# USB_Tester_STM32F429-DISC1.net
KiCad netlist of a schematic drawn in EAGLE
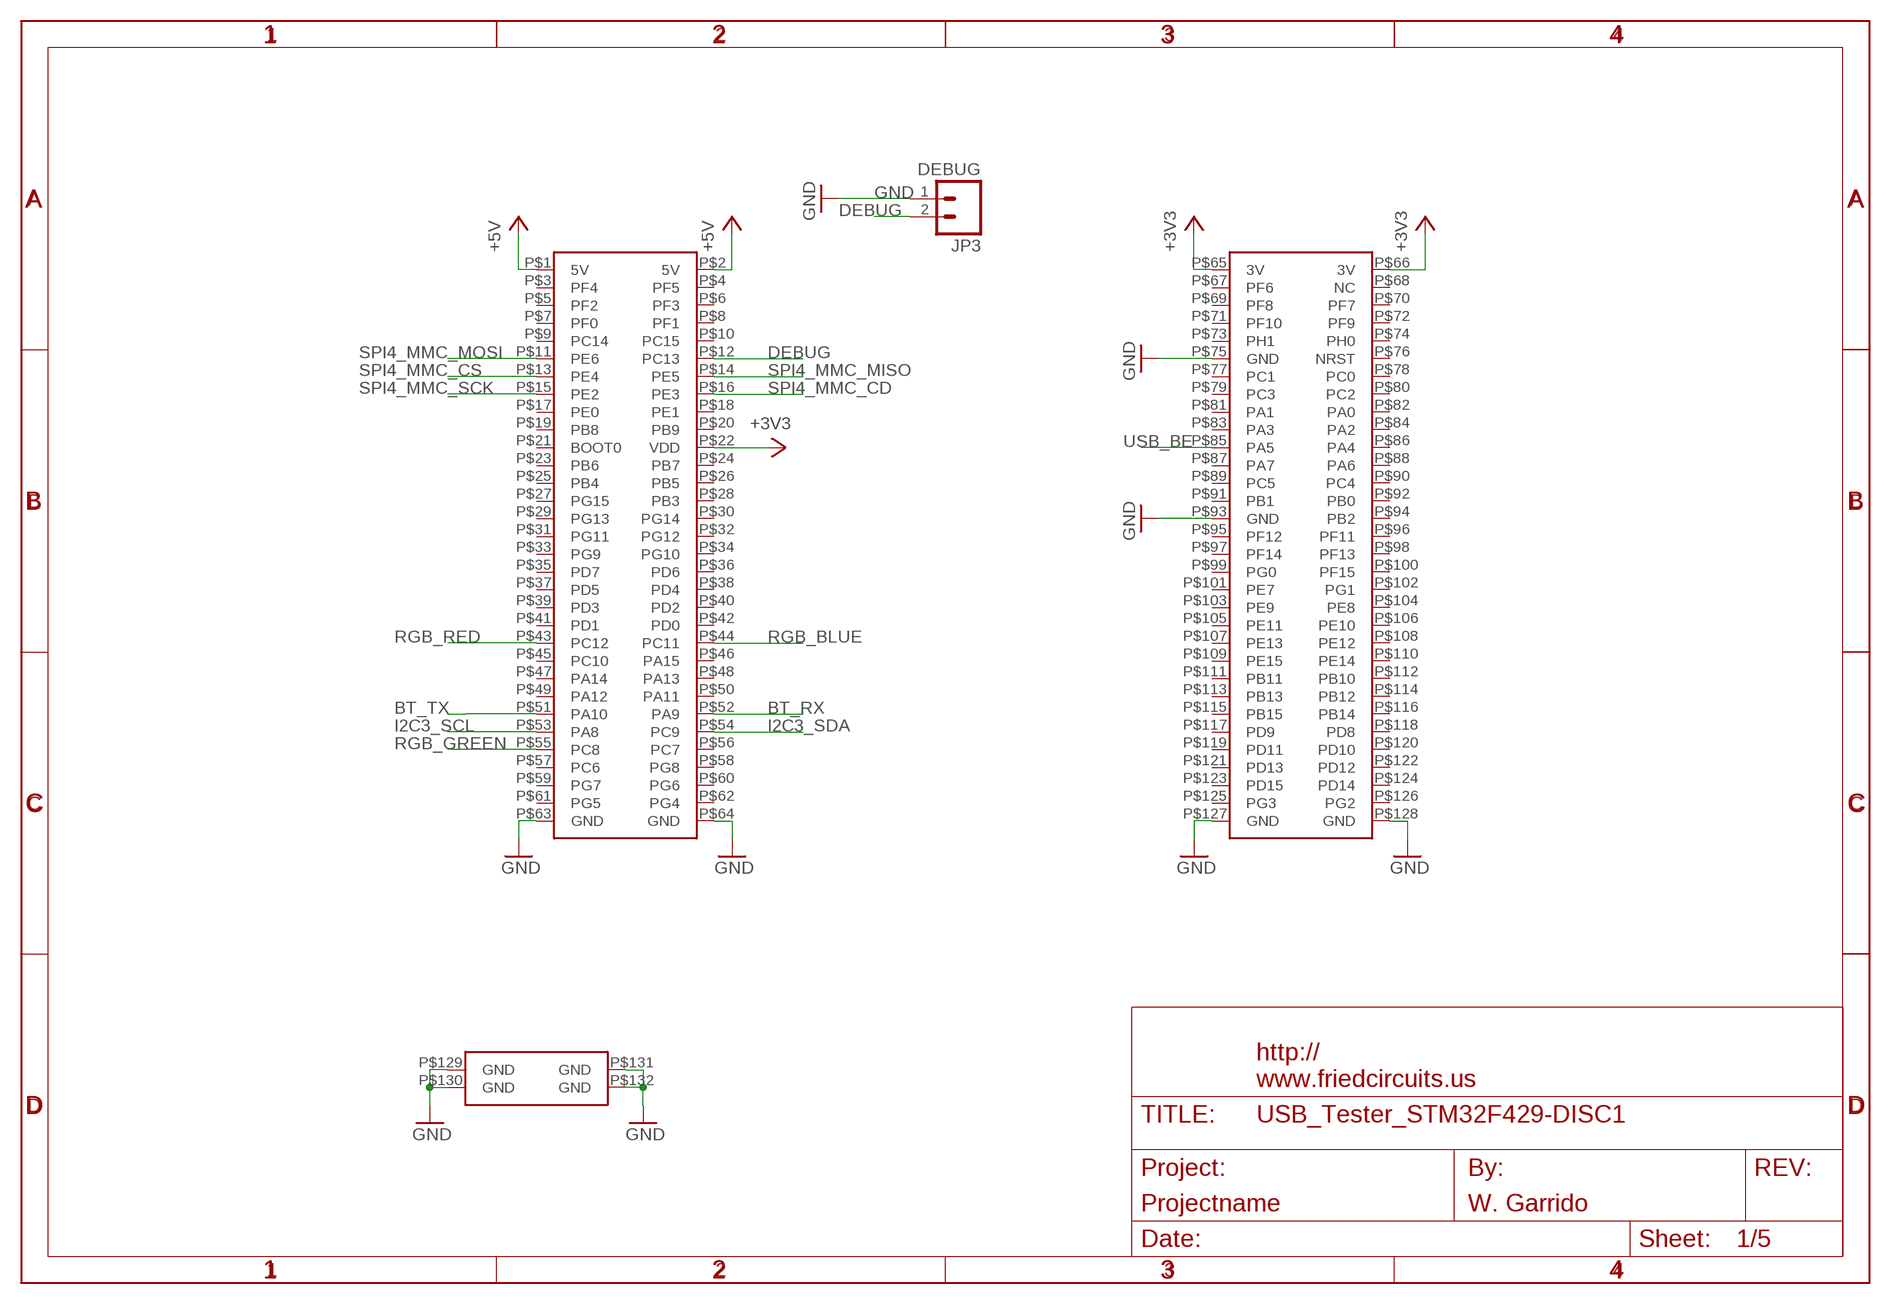
[diagram p0: schematic, sheet 1]
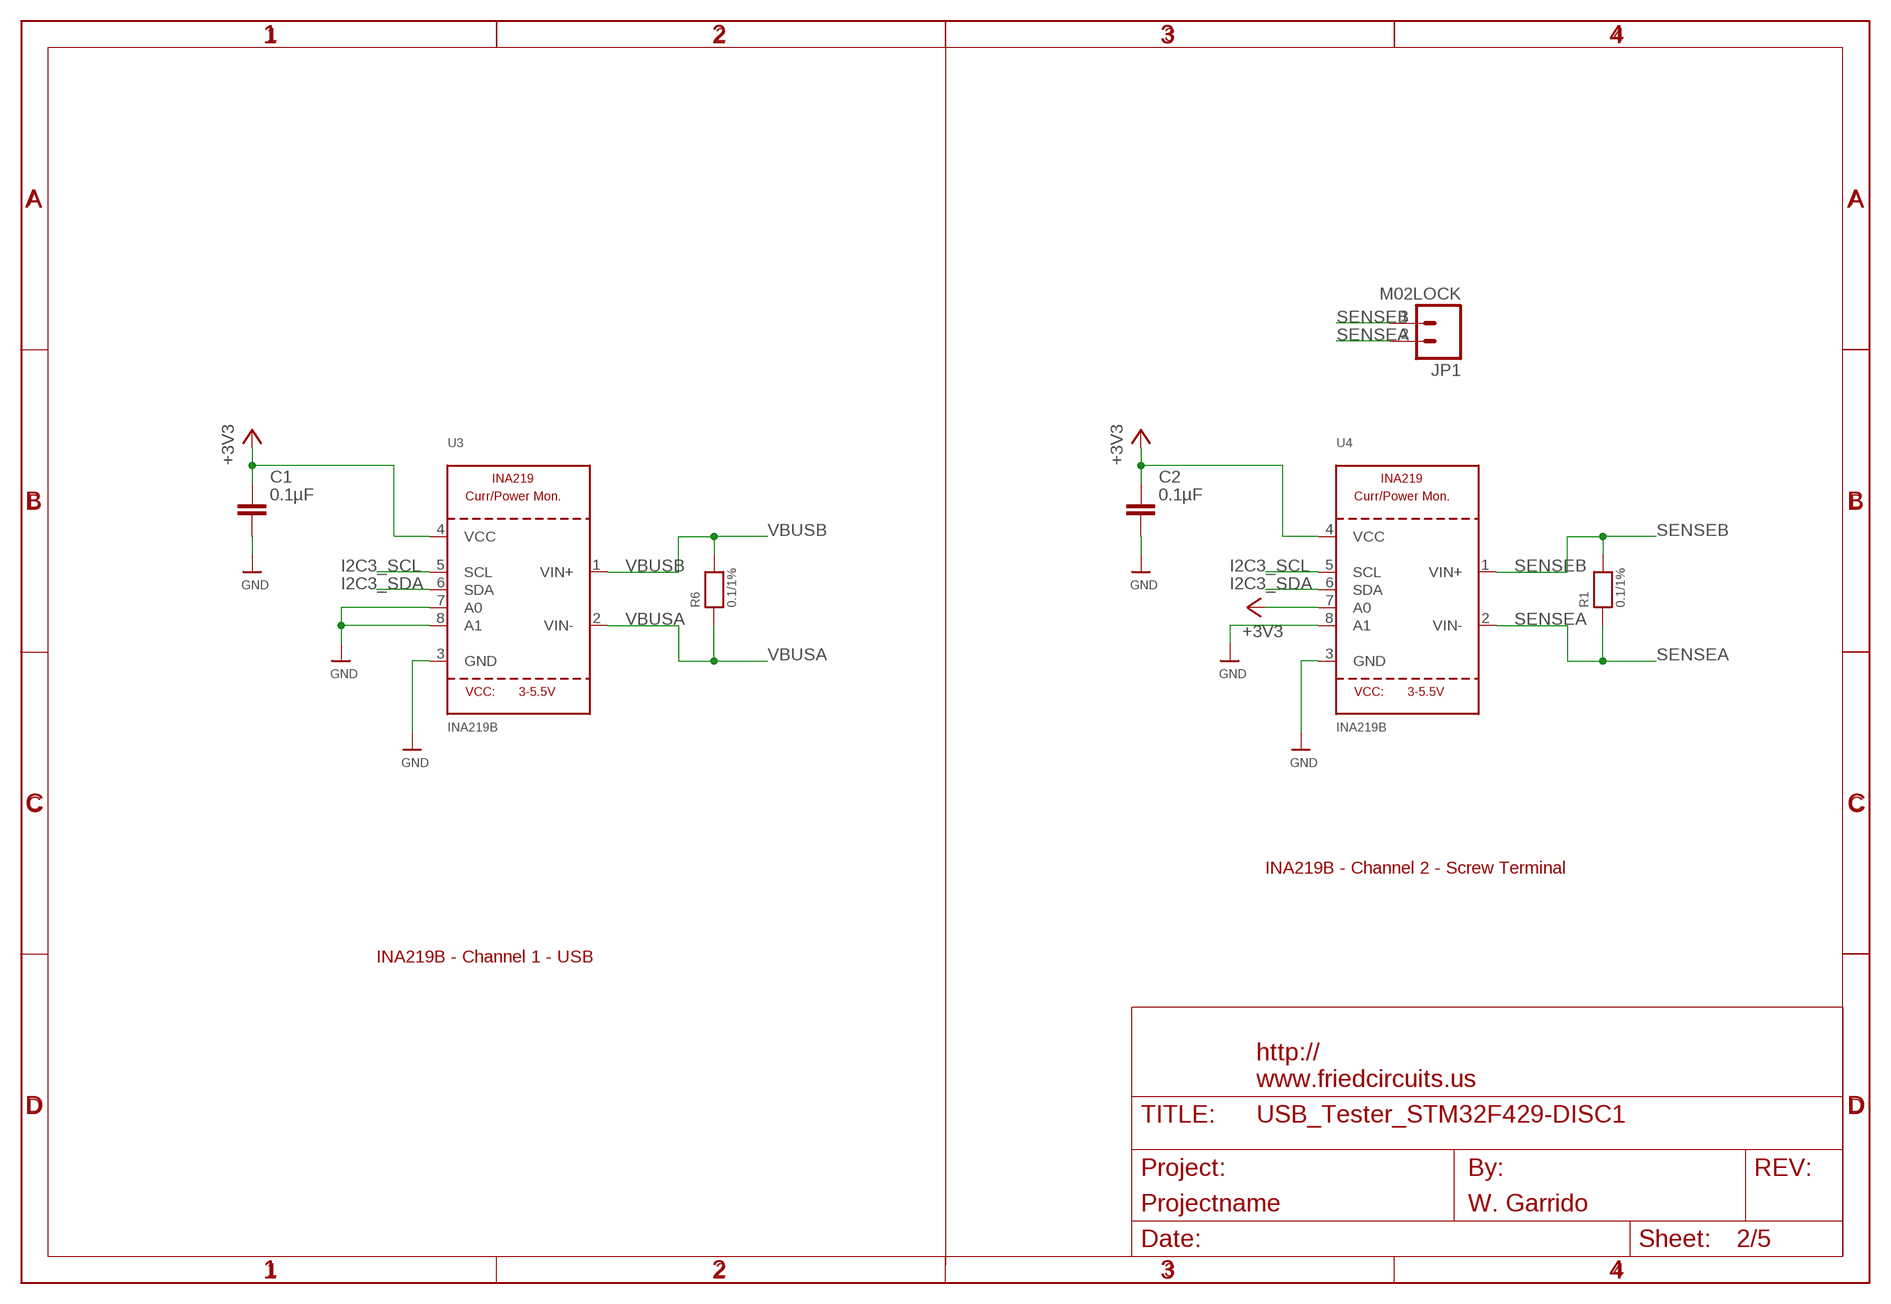
[diagram p1: schematic, sheet 2]
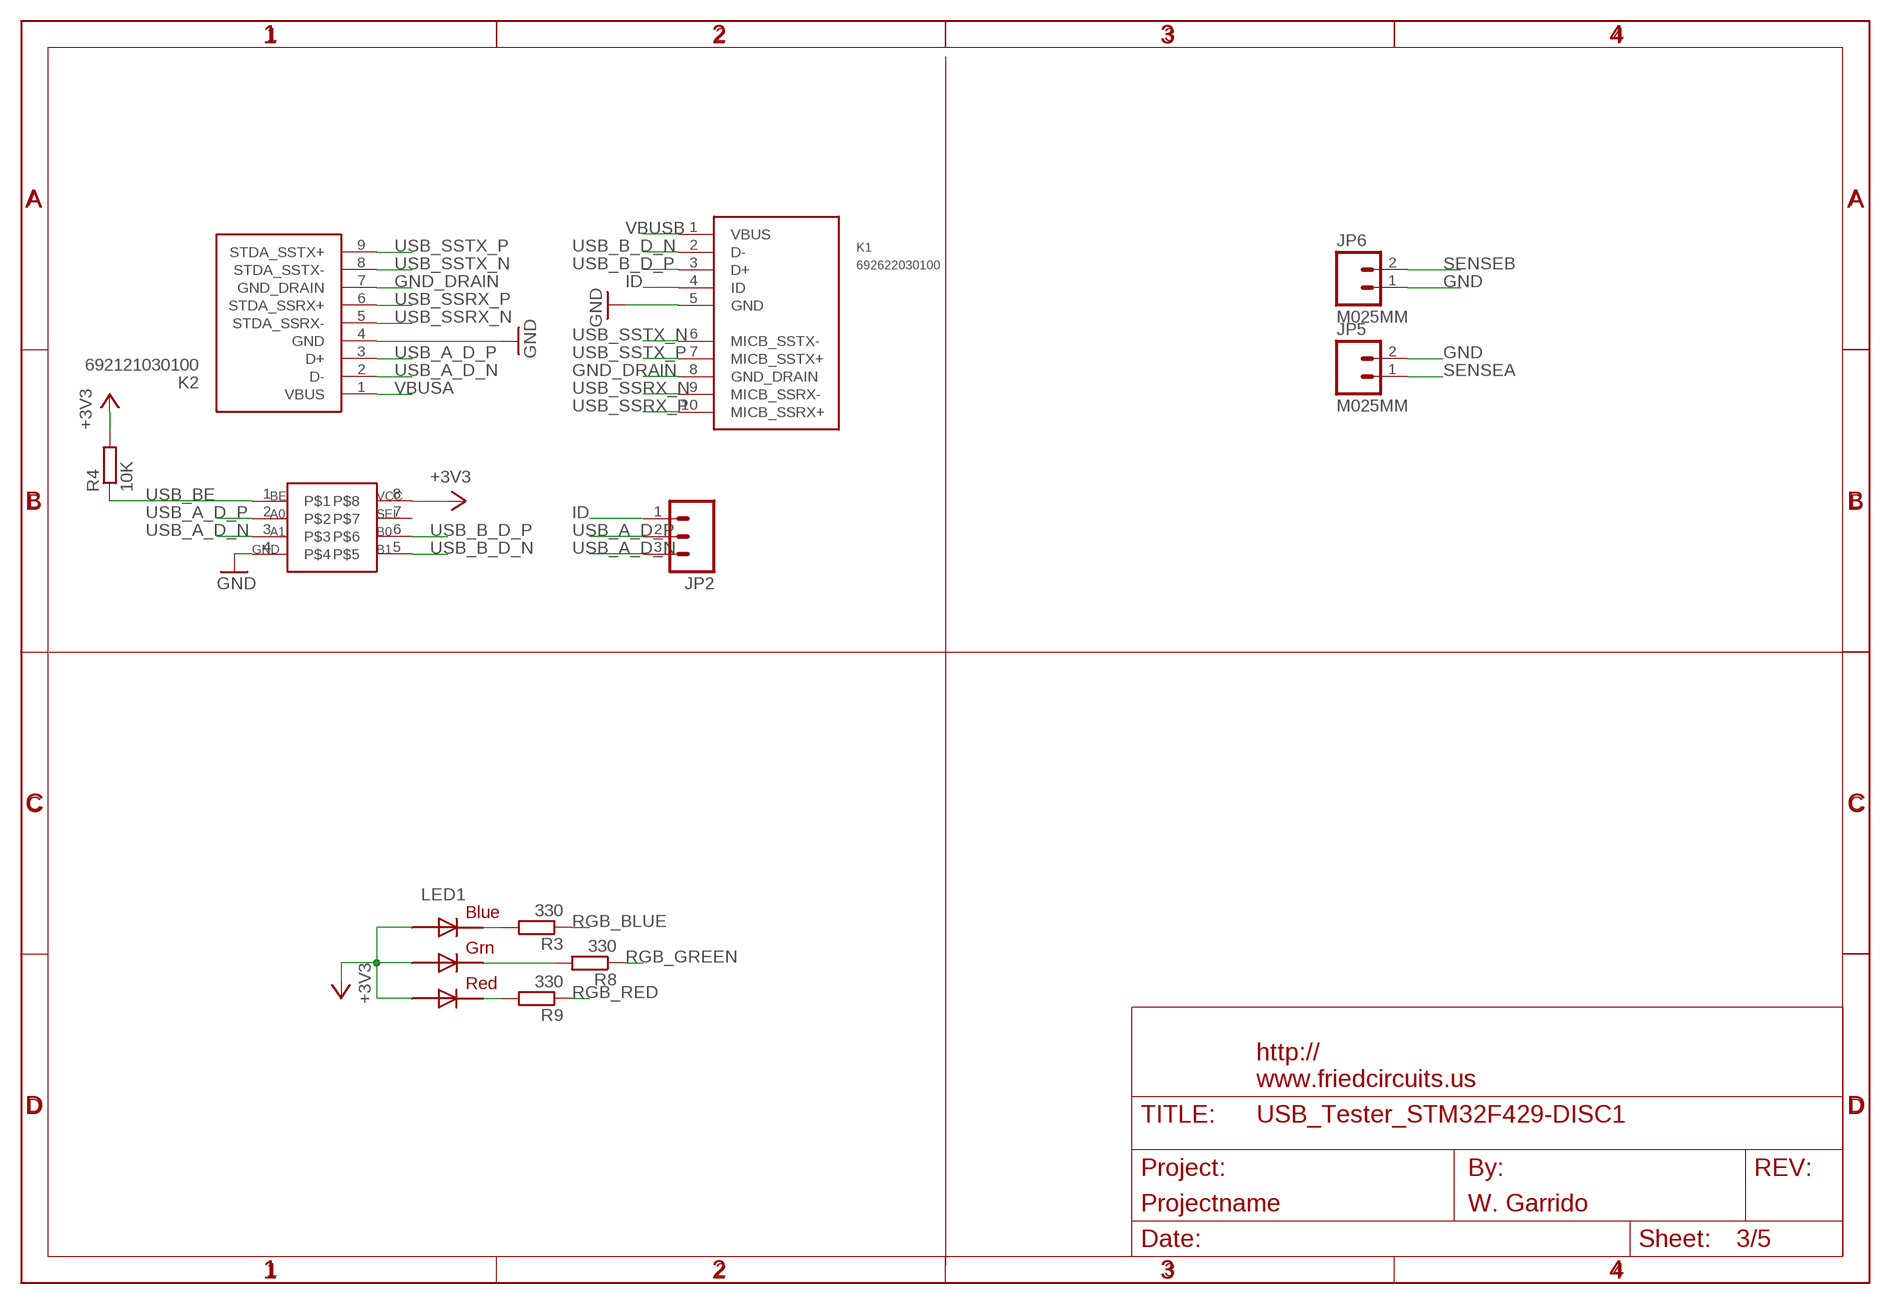
[diagram p2: schematic, sheet 3]
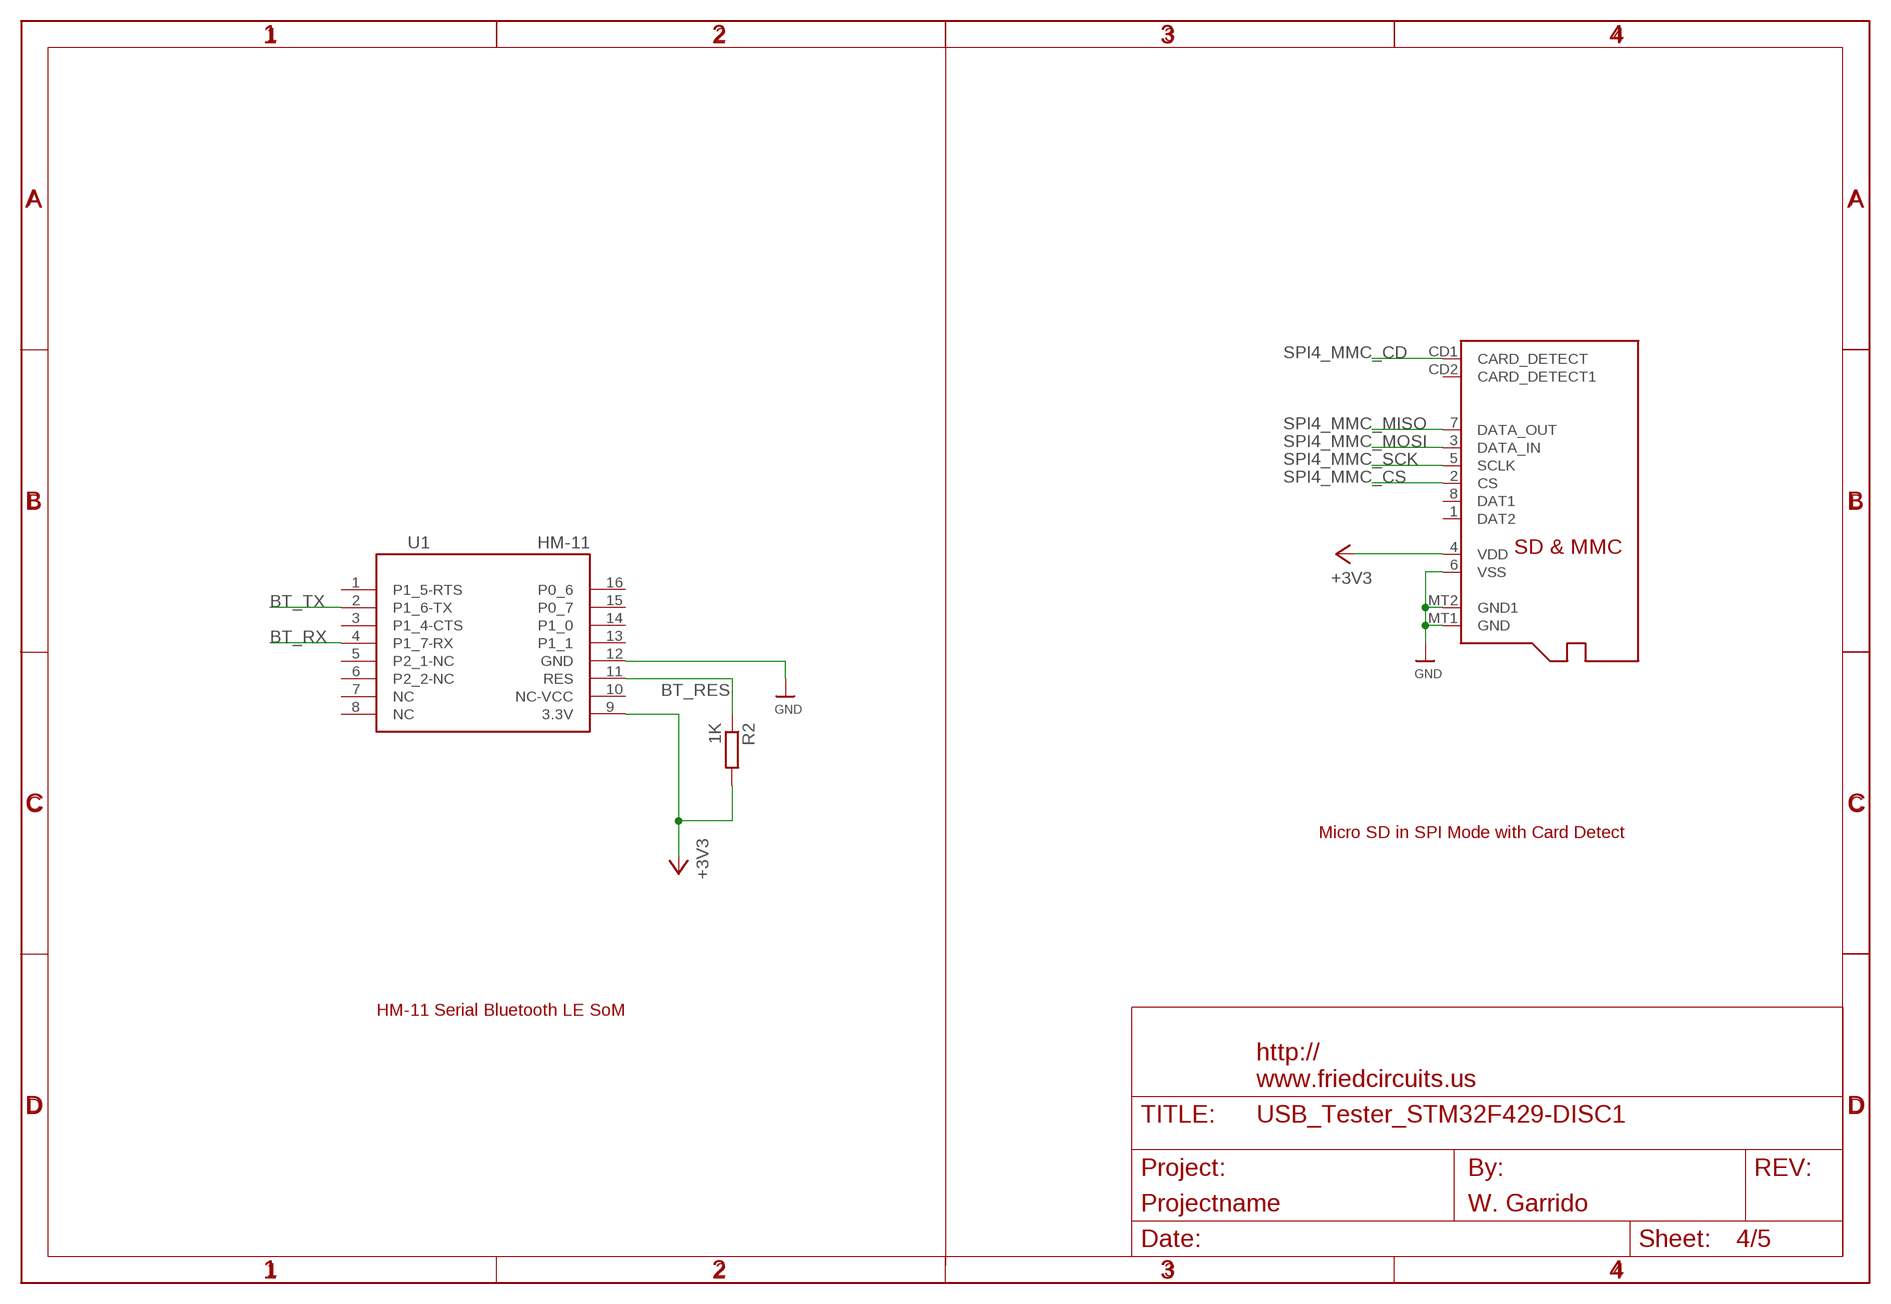
[diagram p3: schematic, sheet 4]
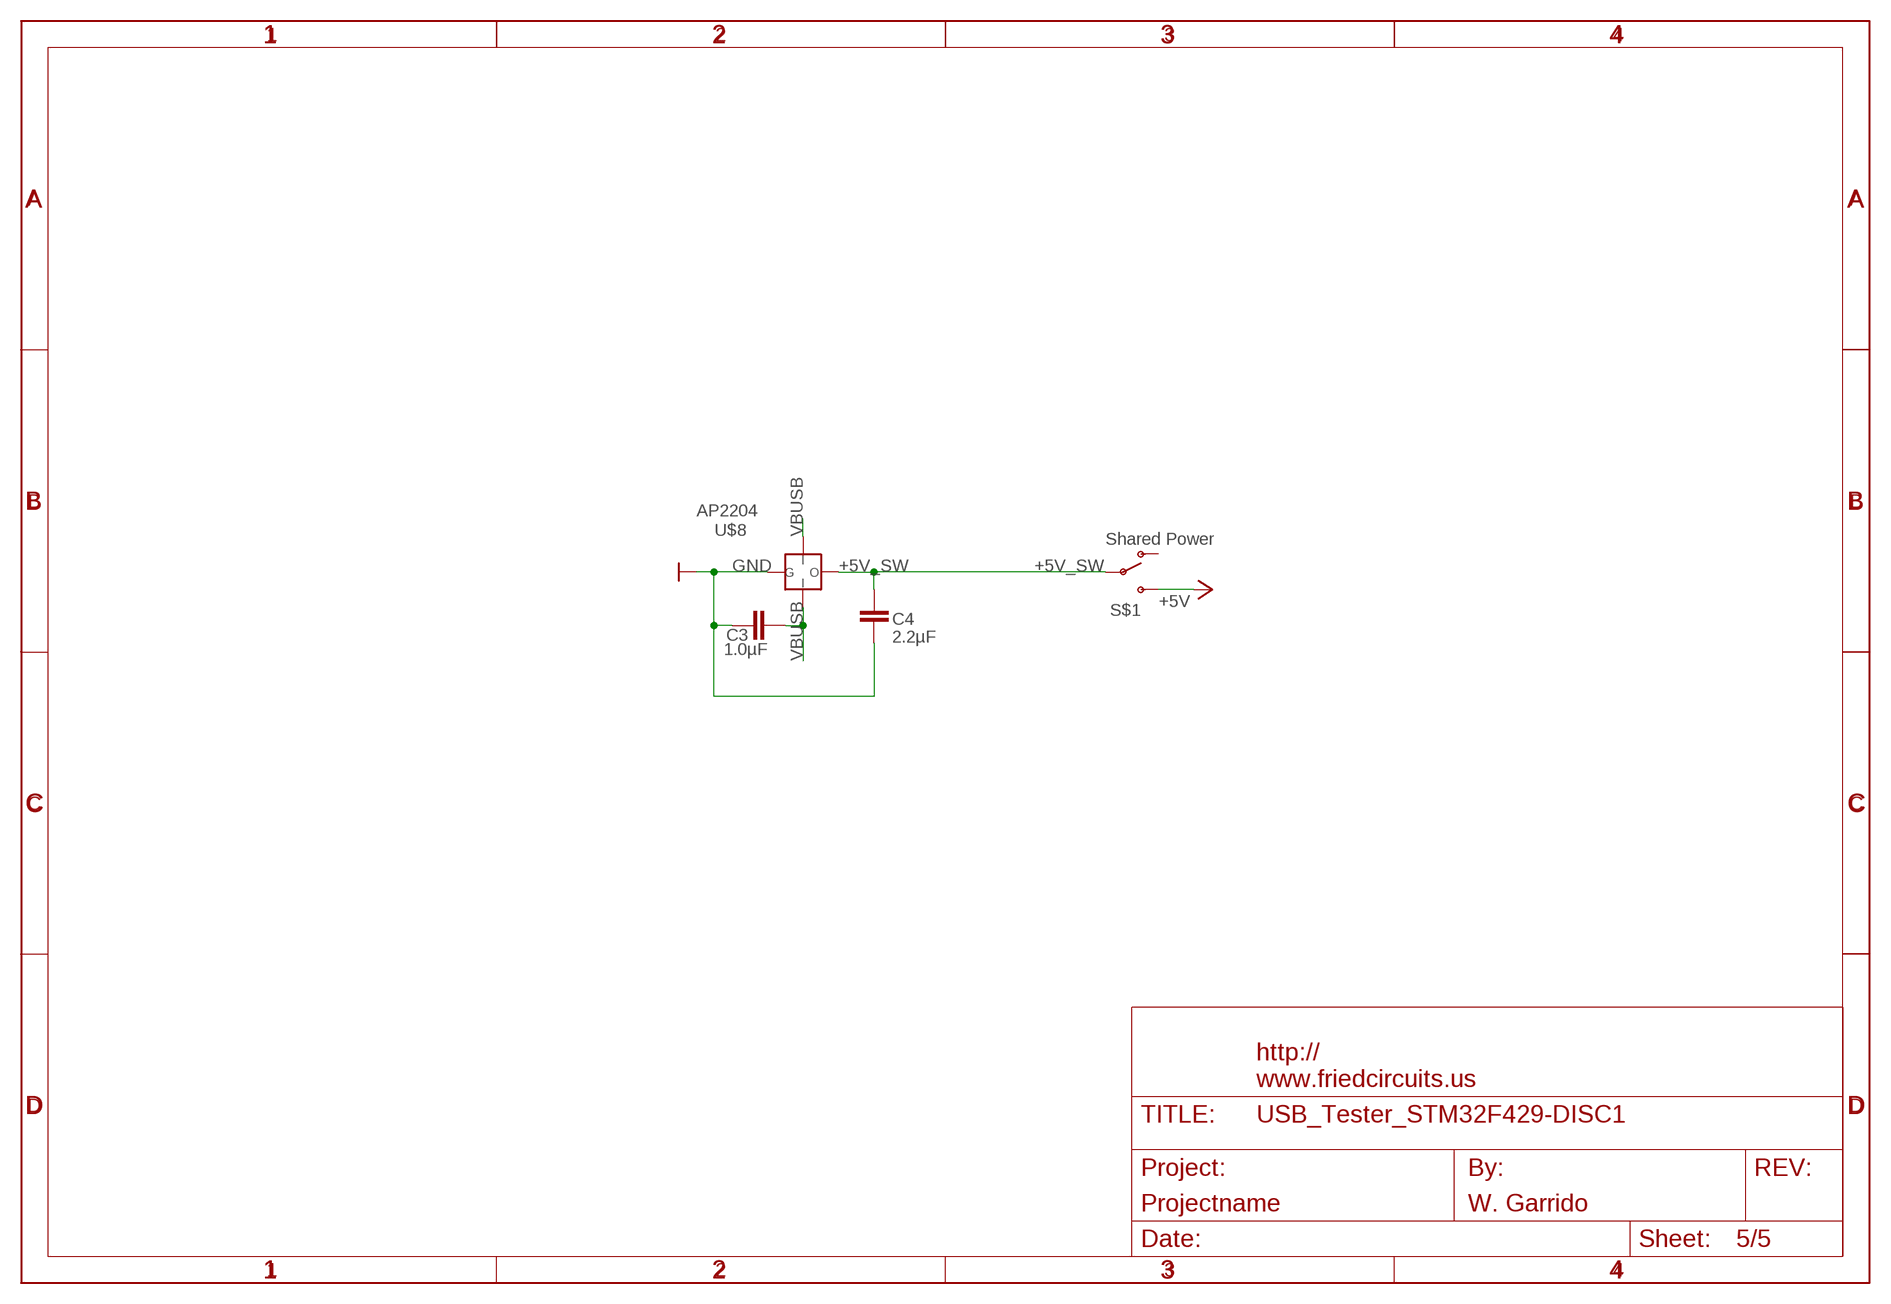
[diagram p4: schematic, sheet 5]

(export (version "E")
  (design (tool "Eeschema 10.0.6"))
  (components
    (comp (ref "C3")
      (value "1.0µF")
      (footprint "eagle-import:C603")
      (libsource (lib "eagle-import") (part "CAPACITOR_NPOL-0603"))
    )
    (comp (ref "C4")
      (value "2.2µF")
      (footprint "eagle-import:C603")
      (libsource (lib "eagle-import") (part "CAPACITOR_NPOL-0603"))
    )
    (comp (ref "S$1")
      (value "Shared Power")
      (footprint "eagle-import:KPS-1290")
      (libsource (lib "eagle-import") (part "SWITCH_SPDT"))
    )
    (comp (ref "U$6")
      (value "FRAME_DINA4_L")
      (footprint "eagle-import:FC_CREDIT")
      (fields (field (name "AUTHOR") "W. Garrido"))
      (libsource (lib "eagle-import") (part "FRAME_DINA4_L"))
    )
    (comp (ref "U$8")
      (value "AP2204")
      (footprint "eagle-import:SOT89-3")
      (libsource (lib "eagle-import") (part "AP2204"))
    )
    (comp (ref "R2")
      (value "1K")
      (footprint "eagle-import:R603")
      (libsource (lib "eagle-import") (part "RESISTOR-0603"))
    )
    (comp (ref "SD_CARD1")
      (value "MICROSD")
      (footprint "eagle-import:MICROSD")
      (libsource (lib "eagle-import") (part "MICROSD"))
    )
    (comp (ref "U$5")
      (value "FRAME_DINA4_L")
      (footprint "eagle-import:FC_CREDIT")
      (fields (field (name "AUTHOR") "W. Garrido"))
      (libsource (lib "eagle-import") (part "FRAME_DINA4_L"))
    )
    (comp (ref "U1")
      (value "HM-11")
      (footprint "eagle-import:HM-11")
      (libsource (lib "eagle-import") (part "HM-11"))
    )
    (comp (ref "JP2")
      (value "M03LOCK")
      (footprint "eagle-import:1X03_LOCK")
      (libsource (lib "eagle-import") (part "M03LOCK"))
    )
    (comp (ref "JP5")
      (value "M025MM")
      (footprint "eagle-import:SCREWTERMINAL-5MM-2")
      (libsource (lib "eagle-import") (part "M025MM"))
    )
    (comp (ref "JP6")
      (value "M025MM")
      (footprint "eagle-import:SCREWTERMINAL-5MM-2")
      (libsource (lib "eagle-import") (part "M025MM"))
    )
    (comp (ref "K1")
      (value "692622030100")
      (footprint "eagle-import:692622030100")
      (libsource (lib "eagle-import") (part "692622030100"))
    )
    (comp (ref "K2")
      (value "692121030100")
      (footprint "eagle-import:692121030100")
      (libsource (lib "eagle-import") (part "692121030100"))
    )
    (comp (ref "LED1")
      (value "RGBLED5050")
      (footprint "eagle-import:RGBLED5050")
      (libsource (lib "eagle-import") (part "RGBLED5050"))
    )
    (comp (ref "R3")
      (value "330")
      (footprint "eagle-import:R603")
      (libsource (lib "eagle-import") (part "RESISTOR-0603"))
    )
    (comp (ref "R4")
      (value "10K")
      (footprint "eagle-import:R603")
      (libsource (lib "eagle-import") (part "RESISTOR-0603"))
    )
    (comp (ref "R8")
      (value "330")
      (footprint "eagle-import:R603")
      (libsource (lib "eagle-import") (part "RESISTOR-0603"))
    )
    (comp (ref "R9")
      (value "330")
      (footprint "eagle-import:R603")
      (libsource (lib "eagle-import") (part "RESISTOR-0603"))
    )
    (comp (ref "U$2")
      (value "FRAME_DINA4_L")
      (footprint "eagle-import:FC_CREDIT")
      (fields (field (name "AUTHOR") "W. Garrido"))
      (libsource (lib "eagle-import") (part "FRAME_DINA4_L"))
    )
    (comp (ref "U$17")
      (value "ADG3242")
      (footprint "eagle-import:SOT23-8")
      (libsource (lib "eagle-import") (part "ADG3242"))
    )
    (comp (ref "C1")
      (value "0.1µF")
      (footprint "eagle-import:C603")
      (libsource (lib "eagle-import") (part "CAPACITOR_NPOL-0603"))
    )
    (comp (ref "C2")
      (value "0.1µF")
      (footprint "eagle-import:C603")
      (libsource (lib "eagle-import") (part "CAPACITOR_NPOL-0603"))
    )
    (comp (ref "JP1")
      (value "M02LOCK")
      (footprint "eagle-import:1X02_LOCK")
      (libsource (lib "eagle-import") (part "M02LOCK"))
    )
    (comp (ref "R1")
      (value "0.1/1%")
      (footprint "eagle-import:2512")
      (libsource (lib "eagle-import") (part "RESISTOR2512"))
    )
    (comp (ref "R6")
      (value "0.1/1%")
      (footprint "eagle-import:2512")
      (libsource (lib "eagle-import") (part "RESISTOR2512"))
    )
    (comp (ref "U$4")
      (value "FRAME_DINA4_L")
      (footprint "eagle-import:FC_CREDIT")
      (fields (field (name "AUTHOR") "W. Garrido"))
      (libsource (lib "eagle-import") (part "FRAME_DINA4_L"))
    )
    (comp (ref "U3")
      (value "INA219B")
      (footprint "eagle-import:SOT23-8")
      (libsource (lib "eagle-import") (part "INA219"))
    )
    (comp (ref "U4")
      (value "INA219B")
      (footprint "eagle-import:SOT23-8")
      (libsource (lib "eagle-import") (part "INA219"))
    )
    (comp (ref "JP3")
      (value "DEBUG")
      (footprint "eagle-import:1X02_LOCK")
      (libsource (lib "eagle-import") (part "M02LOCK"))
    )
    (comp (ref "U$1")
      (value "STM32F429-DISCO")
      (footprint "eagle-import:STM32F429-DISCO")
      (libsource (lib "eagle-import") (part "STM32F429-DISCO"))
    )
    (comp (ref "U$3")
      (value "FRAME_DINA4_L")
      (footprint "eagle-import:FC_CREDIT")
      (fields (field (name "AUTHOR") "W. Garrido"))
      (libsource (lib "eagle-import") (part "FRAME_DINA4_L"))
    )
  )
  (nets
    (net (code "1") (name "+3V3") (class "Default")
      (node (ref "C1") (pin "1") (pinfunction "1_1") (pintype "passive"))
      (node (ref "C2") (pin "1") (pinfunction "1_1") (pintype "passive"))
      (node (ref "LED1") (pin "1") (pinfunction "GREEN_A_1") (pintype "bidirectional"))
      (node (ref "LED1") (pin "2") (pinfunction "RED_A_2") (pintype "bidirectional"))
      (node (ref "LED1") (pin "3") (pinfunction "BLUE_A_3") (pintype "bidirectional"))
      (node (ref "R2") (pin "2") (pinfunction "2_2") (pintype "passive"))
      (node (ref "R4") (pin "2") (pinfunction "2_2") (pintype "passive"))
      (node (ref "SD_CARD1") (pin "4") (pinfunction "VDD_4") (pintype "power_in"))
      (node (ref "U$1") (pin "P$22") (pinfunction "VDD_P$22") (pintype "bidirectional"))
      (node (ref "U$1") (pin "P$65") (pinfunction "3V_P$65") (pintype "bidirectional"))
      (node (ref "U$1") (pin "P$66") (pinfunction "3V_P$66") (pintype "bidirectional"))
      (node (ref "U$17") (pin "8") (pinfunction "P$8_8") (pintype "power_in"))
      (node (ref "U1") (pin "9") (pinfunction "3.3V_9") (pintype "bidirectional"))
      (node (ref "U3") (pin "4") (pinfunction "VCC_4") (pintype "bidirectional"))
      (node (ref "U4") (pin "4") (pinfunction "VCC_4") (pintype "bidirectional"))
      (node (ref "U4") (pin "7") (pinfunction "A0_7") (pintype "bidirectional"))
    )
    (net (code "2") (name "+5V") (class "Default")
      (node (ref "S$1") (pin "S") (pinfunction "S_S") (pintype "passive"))
      (node (ref "U$1") (pin "P$1") (pinfunction "5V_P$1") (pintype "bidirectional"))
      (node (ref "U$1") (pin "P$2") (pinfunction "5V_P$2") (pintype "bidirectional"))
    )
    (net (code "3") (name "+5V_SW") (class "Default")
      (node (ref "C4") (pin "1") (pinfunction "1_1") (pintype "passive"))
      (node (ref "S$1") (pin "P") (pinfunction "P_P") (pintype "passive"))
      (node (ref "U$8") (pin "3") (pinfunction "O_3") (pintype "output"))
    )
    (net (code "4") (name "BT_RES") (class "Default")
      (node (ref "R2") (pin "1") (pinfunction "1_1") (pintype "passive"))
      (node (ref "U1") (pin "11") (pinfunction "RES_11") (pintype "bidirectional"))
    )
    (net (code "5") (name "BT_RX") (class "Default")
      (node (ref "U$1") (pin "P$52") (pinfunction "PA9_P$52") (pintype "bidirectional"))
      (node (ref "U1") (pin "4") (pinfunction "P1_7-RX_4") (pintype "bidirectional"))
    )
    (net (code "6") (name "BT_TX") (class "Default")
      (node (ref "U$1") (pin "P$51") (pinfunction "PA10_P$51") (pintype "bidirectional"))
      (node (ref "U1") (pin "2") (pinfunction "P1_6-TX_2") (pintype "bidirectional"))
    )
    (net (code "7") (name "DEBUG") (class "Default")
      (node (ref "JP3") (pin "2") (pinfunction "2_2") (pintype "passive"))
      (node (ref "U$1") (pin "P$12") (pinfunction "PC13_P$12") (pintype "bidirectional"))
    )
    (net (code "8") (name "GND") (class "Default")
      (node (ref "C1") (pin "2") (pinfunction "2_2") (pintype "passive"))
      (node (ref "C2") (pin "2") (pinfunction "2_2") (pintype "passive"))
      (node (ref "C3") (pin "2") (pinfunction "2_2") (pintype "passive"))
      (node (ref "C4") (pin "2") (pinfunction "2_2") (pintype "passive"))
      (node (ref "JP3") (pin "1") (pinfunction "1_1") (pintype "passive"))
      (node (ref "JP5") (pin "2") (pinfunction "2_2") (pintype "passive"))
      (node (ref "JP6") (pin "1") (pinfunction "1_1") (pintype "passive"))
      (node (ref "K1") (pin "5") (pinfunction "GND_5") (pintype "bidirectional"))
      (node (ref "K2") (pin "4") (pinfunction "GND_4") (pintype "bidirectional"))
      (node (ref "SD_CARD1") (pin "6") (pinfunction "VSS_6") (pintype "power_in"))
      (node (ref "SD_CARD1") (pin "MT1") (pinfunction "GND_MT1") (pintype "power_in"))
      (node (ref "SD_CARD1") (pin "MT2") (pinfunction "GND1_MT2") (pintype "power_in"))
      (node (ref "U$1") (pin "P$127") (pinfunction "GND_P$127") (pintype "bidirectional"))
      (node (ref "U$1") (pin "P$128") (pinfunction "GND_P$128") (pintype "bidirectional"))
      (node (ref "U$1") (pin "P$129") (pinfunction "GND_P$129") (pintype "bidirectional"))
      (node (ref "U$1") (pin "P$130") (pinfunction "GND_P$130") (pintype "bidirectional"))
      (node (ref "U$1") (pin "P$131") (pinfunction "GND_P$131") (pintype "bidirectional"))
      (node (ref "U$1") (pin "P$132") (pinfunction "GND_P$132") (pintype "bidirectional"))
      (node (ref "U$1") (pin "P$63") (pinfunction "GND_P$63") (pintype "bidirectional"))
      (node (ref "U$1") (pin "P$64") (pinfunction "GND_P$64") (pintype "bidirectional"))
      (node (ref "U$1") (pin "P$75") (pinfunction "GND_P$75") (pintype "bidirectional"))
      (node (ref "U$1") (pin "P$93") (pinfunction "GND_P$93") (pintype "bidirectional"))
      (node (ref "U$17") (pin "4") (pinfunction "P$4_4") (pintype "power_in"))
      (node (ref "U$8") (pin "1") (pinfunction "G_1") (pintype "power_in"))
      (node (ref "U1") (pin "12") (pinfunction "GND_12") (pintype "bidirectional"))
      (node (ref "U3") (pin "3") (pinfunction "GND_3") (pintype "bidirectional"))
      (node (ref "U3") (pin "7") (pinfunction "A0_7") (pintype "bidirectional"))
      (node (ref "U3") (pin "8") (pinfunction "A1_8") (pintype "bidirectional"))
      (node (ref "U4") (pin "3") (pinfunction "GND_3") (pintype "bidirectional"))
      (node (ref "U4") (pin "8") (pinfunction "A1_8") (pintype "bidirectional"))
    )
    (net (code "9") (name "GND_DRAIN") (class "Default")
      (node (ref "K1") (pin "8") (pinfunction "GND_DRAIN_8") (pintype "bidirectional"))
      (node (ref "K2") (pin "7") (pinfunction "GND_DRAIN_7") (pintype "bidirectional"))
    )
    (net (code "10") (name "I2C3_SCL") (class "Default")
      (node (ref "U$1") (pin "P$53") (pinfunction "PA8_P$53") (pintype "bidirectional"))
      (node (ref "U3") (pin "5") (pinfunction "SCL_5") (pintype "bidirectional"))
      (node (ref "U4") (pin "5") (pinfunction "SCL_5") (pintype "bidirectional"))
    )
    (net (code "11") (name "I2C3_SDA") (class "Default")
      (node (ref "U$1") (pin "P$54") (pinfunction "PC9_P$54") (pintype "bidirectional"))
      (node (ref "U3") (pin "6") (pinfunction "SDA_6") (pintype "bidirectional"))
      (node (ref "U4") (pin "6") (pinfunction "SDA_6") (pintype "bidirectional"))
    )
    (net (code "12") (name "ID") (class "Default")
      (node (ref "JP2") (pin "1") (pinfunction "1_1") (pintype "passive"))
      (node (ref "K1") (pin "4") (pinfunction "ID_4") (pintype "bidirectional"))
    )
    (net (code "13") (name "Net-(LED1-BLUE_C)") (class "Default")
      (node (ref "LED1") (pin "4") (pinfunction "BLUE_C_4") (pintype "bidirectional"))
      (node (ref "R3") (pin "2") (pinfunction "2_2") (pintype "passive"))
    )
    (net (code "14") (name "Net-(LED1-GREEN_C)") (class "Default")
      (node (ref "LED1") (pin "6") (pinfunction "GREEN_C_6") (pintype "bidirectional"))
      (node (ref "R8") (pin "2") (pinfunction "2_2") (pintype "passive"))
    )
    (net (code "15") (name "Net-(LED1-RED_C)") (class "Default")
      (node (ref "LED1") (pin "5") (pinfunction "RED_C_5") (pintype "bidirectional"))
      (node (ref "R9") (pin "2") (pinfunction "2_2") (pintype "passive"))
    )
    (net (code "16") (name "RGB_BLUE") (class "Default")
      (node (ref "R3") (pin "1") (pinfunction "1_1") (pintype "passive"))
      (node (ref "U$1") (pin "P$44") (pinfunction "PC11_P$44") (pintype "bidirectional"))
    )
    (net (code "17") (name "RGB_GREEN") (class "Default")
      (node (ref "R8") (pin "1") (pinfunction "1_1") (pintype "passive"))
      (node (ref "U$1") (pin "P$55") (pinfunction "PC8_P$55") (pintype "bidirectional"))
    )
    (net (code "18") (name "RGB_RED") (class "Default")
      (node (ref "R9") (pin "1") (pinfunction "1_1") (pintype "passive"))
      (node (ref "U$1") (pin "P$43") (pinfunction "PC12_P$43") (pintype "bidirectional"))
    )
    (net (code "19") (name "SENSEA") (class "Default")
      (node (ref "JP1") (pin "2") (pinfunction "2_2") (pintype "passive"))
      (node (ref "JP5") (pin "1") (pinfunction "1_1") (pintype "passive"))
      (node (ref "R1") (pin "1") (pinfunction "1_1") (pintype "passive"))
      (node (ref "U4") (pin "2") (pinfunction "VIN-_2") (pintype "bidirectional"))
    )
    (net (code "20") (name "SENSEB") (class "Default")
      (node (ref "JP1") (pin "1") (pinfunction "1_1") (pintype "passive"))
      (node (ref "JP6") (pin "2") (pinfunction "2_2") (pintype "passive"))
      (node (ref "R1") (pin "2") (pinfunction "2_2") (pintype "passive"))
      (node (ref "U4") (pin "1") (pinfunction "VIN+_1") (pintype "bidirectional"))
    )
    (net (code "21") (name "SPI4_MMC_CD") (class "Default")
      (node (ref "SD_CARD1") (pin "CD1") (pinfunction "CARD_DETECT_CD1") (pintype "passive"))
      (node (ref "U$1") (pin "P$16") (pinfunction "PE3_P$16") (pintype "bidirectional"))
    )
    (net (code "22") (name "SPI4_MMC_CS") (class "Default")
      (node (ref "SD_CARD1") (pin "2") (pinfunction "CS_2") (pintype "input"))
      (node (ref "U$1") (pin "P$13") (pinfunction "PE4_P$13") (pintype "bidirectional"))
    )
    (net (code "23") (name "SPI4_MMC_MISO") (class "Default")
      (node (ref "SD_CARD1") (pin "7") (pinfunction "DATA_OUT_7") (pintype "output"))
      (node (ref "U$1") (pin "P$14") (pinfunction "PE5_P$14") (pintype "bidirectional"))
    )
    (net (code "24") (name "SPI4_MMC_MOSI") (class "Default")
      (node (ref "SD_CARD1") (pin "3") (pinfunction "DATA_IN_3") (pintype "input"))
      (node (ref "U$1") (pin "P$11") (pinfunction "PE6_P$11") (pintype "bidirectional"))
    )
    (net (code "25") (name "SPI4_MMC_SCK") (class "Default")
      (node (ref "SD_CARD1") (pin "5") (pinfunction "SCLK_5") (pintype "input"))
      (node (ref "U$1") (pin "P$15") (pinfunction "PE2_P$15") (pintype "bidirectional"))
    )
    (net (code "26") (name "USB_A_D_N") (class "Default")
      (node (ref "JP2") (pin "3") (pinfunction "3_3") (pintype "passive"))
      (node (ref "K2") (pin "2") (pinfunction "D-_2") (pintype "bidirectional"))
      (node (ref "U$17") (pin "3") (pinfunction "P$3_3") (pintype "bidirectional"))
    )
    (net (code "27") (name "USB_A_D_P") (class "Default")
      (node (ref "JP2") (pin "2") (pinfunction "2_2") (pintype "passive"))
      (node (ref "K2") (pin "3") (pinfunction "D+_3") (pintype "bidirectional"))
      (node (ref "U$17") (pin "2") (pinfunction "P$2_2") (pintype "bidirectional"))
    )
    (net (code "28") (name "USB_BE") (class "Default")
      (node (ref "R4") (pin "1") (pinfunction "1_1") (pintype "passive"))
      (node (ref "U$1") (pin "P$85") (pinfunction "PA5_P$85") (pintype "bidirectional"))
      (node (ref "U$17") (pin "1") (pinfunction "P$1_1") (pintype "input"))
    )
    (net (code "29") (name "USB_B_D_N") (class "Default")
      (node (ref "K1") (pin "2") (pinfunction "D-_2") (pintype "bidirectional"))
      (node (ref "U$17") (pin "5") (pinfunction "P$5_5") (pintype "bidirectional"))
    )
    (net (code "30") (name "USB_B_D_P") (class "Default")
      (node (ref "K1") (pin "3") (pinfunction "D+_3") (pintype "bidirectional"))
      (node (ref "U$17") (pin "6") (pinfunction "P$6_6") (pintype "bidirectional"))
    )
    (net (code "31") (name "USB_SSRX_N") (class "Default")
      (node (ref "K1") (pin "9") (pinfunction "MICB_SSRX-_9") (pintype "bidirectional"))
      (node (ref "K2") (pin "5") (pinfunction "STDA_SSRX-_5") (pintype "bidirectional"))
    )
    (net (code "32") (name "USB_SSRX_P") (class "Default")
      (node (ref "K1") (pin "10") (pinfunction "MICB_SSRX+_10") (pintype "bidirectional"))
      (node (ref "K2") (pin "6") (pinfunction "STDA_SSRX+_6") (pintype "bidirectional"))
    )
    (net (code "33") (name "USB_SSTX_N") (class "Default")
      (node (ref "K1") (pin "6") (pinfunction "MICB_SSTX-_6") (pintype "bidirectional"))
      (node (ref "K2") (pin "8") (pinfunction "STDA_SSTX-_8") (pintype "bidirectional"))
    )
    (net (code "34") (name "USB_SSTX_P") (class "Default")
      (node (ref "K1") (pin "7") (pinfunction "MICB_SSTX+_7") (pintype "bidirectional"))
      (node (ref "K2") (pin "9") (pinfunction "STDA_SSTX+_9") (pintype "bidirectional"))
    )
    (net (code "35") (name "VBUSA") (class "Default")
      (node (ref "K2") (pin "1") (pinfunction "VBUS_1") (pintype "bidirectional"))
      (node (ref "R6") (pin "1") (pinfunction "1_1") (pintype "passive"))
      (node (ref "U3") (pin "2") (pinfunction "VIN-_2") (pintype "bidirectional"))
    )
    (net (code "36") (name "VBUSB") (class "Default")
      (node (ref "C3") (pin "1") (pinfunction "1_1") (pintype "passive"))
      (node (ref "K1") (pin "1") (pinfunction "VBUS_1") (pintype "bidirectional"))
      (node (ref "R6") (pin "2") (pinfunction "2_2") (pintype "passive"))
      (node (ref "U$8") (pin "2") (pinfunction "VIN_2") (pintype "input"))
      (node (ref "U$8") (pin "4") (pinfunction "VIN_4") (pintype "input"))
      (node (ref "U3") (pin "1") (pinfunction "VIN+_1") (pintype "bidirectional"))
    )
    (net (code "37") (name "unconnected-(S$1-PadO)") (class "Default")
      (node (ref "S$1") (pin "O") (pinfunction "O_O") (pintype "passive"))
    )
    (net (code "38") (name "unconnected-(SD_CARD1-CARD_DETECT1-PadCD2)") (class "Default")
      (node (ref "SD_CARD1") (pin "CD2") (pinfunction "CARD_DETECT1_CD2") (pintype "passive"))
    )
    (net (code "39") (name "unconnected-(SD_CARD1-DAT1-Pad8)") (class "Default")
      (node (ref "SD_CARD1") (pin "8") (pinfunction "DAT1_8") (pintype "bidirectional"))
    )
    (net (code "40") (name "unconnected-(SD_CARD1-DAT2-Pad1)") (class "Default")
      (node (ref "SD_CARD1") (pin "1") (pinfunction "DAT2_1") (pintype "bidirectional"))
    )
    (net (code "41") (name "unconnected-(U$1A-BOOT0-PadP$21)") (class "Default")
      (node (ref "U$1") (pin "P$21") (pinfunction "BOOT0_P$21") (pintype "bidirectional"))
    )
    (net (code "42") (name "unconnected-(U$1A-PA11-PadP$50)") (class "Default")
      (node (ref "U$1") (pin "P$50") (pinfunction "PA11_P$50") (pintype "bidirectional"))
    )
    (net (code "43") (name "unconnected-(U$1A-PA12-PadP$49)") (class "Default")
      (node (ref "U$1") (pin "P$49") (pinfunction "PA12_P$49") (pintype "bidirectional"))
    )
    (net (code "44") (name "unconnected-(U$1A-PA13-PadP$48)") (class "Default")
      (node (ref "U$1") (pin "P$48") (pinfunction "PA13_P$48") (pintype "bidirectional"))
    )
    (net (code "45") (name "unconnected-(U$1A-PA14-PadP$47)") (class "Default")
      (node (ref "U$1") (pin "P$47") (pinfunction "PA14_P$47") (pintype "bidirectional"))
    )
    (net (code "46") (name "unconnected-(U$1A-PA15-PadP$46)") (class "Default")
      (node (ref "U$1") (pin "P$46") (pinfunction "PA15_P$46") (pintype "bidirectional"))
    )
    (net (code "47") (name "unconnected-(U$1A-PB3-PadP$28)") (class "Default")
      (node (ref "U$1") (pin "P$28") (pinfunction "PB3_P$28") (pintype "bidirectional"))
    )
    (net (code "48") (name "unconnected-(U$1A-PB4-PadP$25)") (class "Default")
      (node (ref "U$1") (pin "P$25") (pinfunction "PB4_P$25") (pintype "bidirectional"))
    )
    (net (code "49") (name "unconnected-(U$1A-PB5-PadP$26)") (class "Default")
      (node (ref "U$1") (pin "P$26") (pinfunction "PB5_P$26") (pintype "bidirectional"))
    )
    (net (code "50") (name "unconnected-(U$1A-PB6-PadP$23)") (class "Default")
      (node (ref "U$1") (pin "P$23") (pinfunction "PB6_P$23") (pintype "bidirectional"))
    )
    (net (code "51") (name "unconnected-(U$1A-PB7-PadP$24)") (class "Default")
      (node (ref "U$1") (pin "P$24") (pinfunction "PB7_P$24") (pintype "bidirectional"))
    )
    (net (code "52") (name "unconnected-(U$1A-PB8-PadP$19)") (class "Default")
      (node (ref "U$1") (pin "P$19") (pinfunction "PB8_P$19") (pintype "bidirectional"))
    )
    (net (code "53") (name "unconnected-(U$1A-PB9-PadP$20)") (class "Default")
      (node (ref "U$1") (pin "P$20") (pinfunction "PB9_P$20") (pintype "bidirectional"))
    )
    (net (code "54") (name "unconnected-(U$1A-PC6-PadP$57)") (class "Default")
      (node (ref "U$1") (pin "P$57") (pinfunction "PC6_P$57") (pintype "bidirectional"))
    )
    (net (code "55") (name "unconnected-(U$1A-PC7-PadP$56)") (class "Default")
      (node (ref "U$1") (pin "P$56") (pinfunction "PC7_P$56") (pintype "bidirectional"))
    )
    (net (code "56") (name "unconnected-(U$1A-PC10-PadP$45)") (class "Default")
      (node (ref "U$1") (pin "P$45") (pinfunction "PC10_P$45") (pintype "bidirectional"))
    )
    (net (code "57") (name "unconnected-(U$1A-PC14-PadP$9)") (class "Default")
      (node (ref "U$1") (pin "P$9") (pinfunction "PC14_P$9") (pintype "bidirectional"))
    )
    (net (code "58") (name "unconnected-(U$1A-PC15-PadP$10)") (class "Default")
      (node (ref "U$1") (pin "P$10") (pinfunction "PC15_P$10") (pintype "bidirectional"))
    )
    (net (code "59") (name "unconnected-(U$1A-PD0-PadP$42)") (class "Default")
      (node (ref "U$1") (pin "P$42") (pinfunction "PD0_P$42") (pintype "bidirectional"))
    )
    (net (code "60") (name "unconnected-(U$1A-PD1-PadP$41)") (class "Default")
      (node (ref "U$1") (pin "P$41") (pinfunction "PD1_P$41") (pintype "bidirectional"))
    )
    (net (code "61") (name "unconnected-(U$1A-PD2-PadP$40)") (class "Default")
      (node (ref "U$1") (pin "P$40") (pinfunction "PD2_P$40") (pintype "bidirectional"))
    )
    (net (code "62") (name "unconnected-(U$1A-PD3-PadP$39)") (class "Default")
      (node (ref "U$1") (pin "P$39") (pinfunction "PD3_P$39") (pintype "bidirectional"))
    )
    (net (code "63") (name "unconnected-(U$1A-PD4-PadP$38)") (class "Default")
      (node (ref "U$1") (pin "P$38") (pinfunction "PD4_P$38") (pintype "bidirectional"))
    )
    (net (code "64") (name "unconnected-(U$1A-PD5-PadP$37)") (class "Default")
      (node (ref "U$1") (pin "P$37") (pinfunction "PD5_P$37") (pintype "bidirectional"))
    )
    (net (code "65") (name "unconnected-(U$1A-PD6-PadP$36)") (class "Default")
      (node (ref "U$1") (pin "P$36") (pinfunction "PD6_P$36") (pintype "bidirectional"))
    )
    (net (code "66") (name "unconnected-(U$1A-PD7-PadP$35)") (class "Default")
      (node (ref "U$1") (pin "P$35") (pinfunction "PD7_P$35") (pintype "bidirectional"))
    )
    (net (code "67") (name "unconnected-(U$1A-PE0-PadP$17)") (class "Default")
      (node (ref "U$1") (pin "P$17") (pinfunction "PE0_P$17") (pintype "bidirectional"))
    )
    (net (code "68") (name "unconnected-(U$1A-PE1-PadP$18)") (class "Default")
      (node (ref "U$1") (pin "P$18") (pinfunction "PE1_P$18") (pintype "bidirectional"))
    )
    (net (code "69") (name "unconnected-(U$1A-PF0-PadP$7)") (class "Default")
      (node (ref "U$1") (pin "P$7") (pinfunction "PF0_P$7") (pintype "bidirectional"))
    )
    (net (code "70") (name "unconnected-(U$1A-PF1-PadP$8)") (class "Default")
      (node (ref "U$1") (pin "P$8") (pinfunction "PF1_P$8") (pintype "bidirectional"))
    )
    (net (code "71") (name "unconnected-(U$1A-PF2-PadP$5)") (class "Default")
      (node (ref "U$1") (pin "P$5") (pinfunction "PF2_P$5") (pintype "bidirectional"))
    )
    (net (code "72") (name "unconnected-(U$1A-PF3-PadP$6)") (class "Default")
      (node (ref "U$1") (pin "P$6") (pinfunction "PF3_P$6") (pintype "bidirectional"))
    )
    (net (code "73") (name "unconnected-(U$1A-PF4-PadP$3)") (class "Default")
      (node (ref "U$1") (pin "P$3") (pinfunction "PF4_P$3") (pintype "bidirectional"))
    )
    (net (code "74") (name "unconnected-(U$1A-PF5-PadP$4)") (class "Default")
      (node (ref "U$1") (pin "P$4") (pinfunction "PF5_P$4") (pintype "bidirectional"))
    )
    (net (code "75") (name "unconnected-(U$1A-PG4-PadP$62)") (class "Default")
      (node (ref "U$1") (pin "P$62") (pinfunction "PG4_P$62") (pintype "bidirectional"))
    )
    (net (code "76") (name "unconnected-(U$1A-PG5-PadP$61)") (class "Default")
      (node (ref "U$1") (pin "P$61") (pinfunction "PG5_P$61") (pintype "bidirectional"))
    )
    (net (code "77") (name "unconnected-(U$1A-PG6-PadP$60)") (class "Default")
      (node (ref "U$1") (pin "P$60") (pinfunction "PG6_P$60") (pintype "bidirectional"))
    )
    (net (code "78") (name "unconnected-(U$1A-PG7-PadP$59)") (class "Default")
      (node (ref "U$1") (pin "P$59") (pinfunction "PG7_P$59") (pintype "bidirectional"))
    )
    (net (code "79") (name "unconnected-(U$1A-PG8-PadP$58)") (class "Default")
      (node (ref "U$1") (pin "P$58") (pinfunction "PG8_P$58") (pintype "bidirectional"))
    )
    (net (code "80") (name "unconnected-(U$1A-PG9-PadP$33)") (class "Default")
      (node (ref "U$1") (pin "P$33") (pinfunction "PG9_P$33") (pintype "bidirectional"))
    )
    (net (code "81") (name "unconnected-(U$1A-PG10-PadP$34)") (class "Default")
      (node (ref "U$1") (pin "P$34") (pinfunction "PG10_P$34") (pintype "bidirectional"))
    )
    (net (code "82") (name "unconnected-(U$1A-PG11-PadP$31)") (class "Default")
      (node (ref "U$1") (pin "P$31") (pinfunction "PG11_P$31") (pintype "bidirectional"))
    )
    (net (code "83") (name "unconnected-(U$1A-PG12-PadP$32)") (class "Default")
      (node (ref "U$1") (pin "P$32") (pinfunction "PG12_P$32") (pintype "bidirectional"))
    )
    (net (code "84") (name "unconnected-(U$1A-PG13-PadP$29)") (class "Default")
      (node (ref "U$1") (pin "P$29") (pinfunction "PG13_P$29") (pintype "bidirectional"))
    )
    (net (code "85") (name "unconnected-(U$1A-PG14-PadP$30)") (class "Default")
      (node (ref "U$1") (pin "P$30") (pinfunction "PG14_P$30") (pintype "bidirectional"))
    )
    (net (code "86") (name "unconnected-(U$1A-PG15-PadP$27)") (class "Default")
      (node (ref "U$1") (pin "P$27") (pinfunction "PG15_P$27") (pintype "bidirectional"))
    )
    (net (code "87") (name "unconnected-(U$1B-NC-PadP$68)") (class "Default")
      (node (ref "U$1") (pin "P$68") (pinfunction "NC_P$68") (pintype "bidirectional"))
    )
    (net (code "88") (name "unconnected-(U$1B-NRST-PadP$76)") (class "Default")
      (node (ref "U$1") (pin "P$76") (pinfunction "NRST_P$76") (pintype "bidirectional"))
    )
    (net (code "89") (name "unconnected-(U$1B-PA0-PadP$82)") (class "Default")
      (node (ref "U$1") (pin "P$82") (pinfunction "PA0_P$82") (pintype "bidirectional"))
    )
    (net (code "90") (name "unconnected-(U$1B-PA1-PadP$81)") (class "Default")
      (node (ref "U$1") (pin "P$81") (pinfunction "PA1_P$81") (pintype "bidirectional"))
    )
    (net (code "91") (name "unconnected-(U$1B-PA2-PadP$84)") (class "Default")
      (node (ref "U$1") (pin "P$84") (pinfunction "PA2_P$84") (pintype "bidirectional"))
    )
    (net (code "92") (name "unconnected-(U$1B-PA3-PadP$83)") (class "Default")
      (node (ref "U$1") (pin "P$83") (pinfunction "PA3_P$83") (pintype "bidirectional"))
    )
    (net (code "93") (name "unconnected-(U$1B-PA4-PadP$86)") (class "Default")
      (node (ref "U$1") (pin "P$86") (pinfunction "PA4_P$86") (pintype "bidirectional"))
    )
    (net (code "94") (name "unconnected-(U$1B-PA6-PadP$88)") (class "Default")
      (node (ref "U$1") (pin "P$88") (pinfunction "PA6_P$88") (pintype "bidirectional"))
    )
    (net (code "95") (name "unconnected-(U$1B-PA7-PadP$87)") (class "Default")
      (node (ref "U$1") (pin "P$87") (pinfunction "PA7_P$87") (pintype "bidirectional"))
    )
    (net (code "96") (name "unconnected-(U$1B-PB0-PadP$92)") (class "Default")
      (node (ref "U$1") (pin "P$92") (pinfunction "PB0_P$92") (pintype "bidirectional"))
    )
    (net (code "97") (name "unconnected-(U$1B-PB1-PadP$91)") (class "Default")
      (node (ref "U$1") (pin "P$91") (pinfunction "PB1_P$91") (pintype "bidirectional"))
    )
    (net (code "98") (name "unconnected-(U$1B-PB2-PadP$94)") (class "Default")
      (node (ref "U$1") (pin "P$94") (pinfunction "PB2_P$94") (pintype "bidirectional"))
    )
    (net (code "99") (name "unconnected-(U$1B-PB10-PadP$112)") (class "Default")
      (node (ref "U$1") (pin "P$112") (pinfunction "PB10_P$112") (pintype "bidirectional"))
    )
    (net (code "100") (name "unconnected-(U$1B-PB11-PadP$111)") (class "Default")
      (node (ref "U$1") (pin "P$111") (pinfunction "PB11_P$111") (pintype "bidirectional"))
    )
    (net (code "101") (name "unconnected-(U$1B-PB12-PadP$114)") (class "Default")
      (node (ref "U$1") (pin "P$114") (pinfunction "PB12_P$114") (pintype "bidirectional"))
    )
    (net (code "102") (name "unconnected-(U$1B-PB13-PadP$113)") (class "Default")
      (node (ref "U$1") (pin "P$113") (pinfunction "PB13_P$113") (pintype "bidirectional"))
    )
    (net (code "103") (name "unconnected-(U$1B-PB14-PadP$116)") (class "Default")
      (node (ref "U$1") (pin "P$116") (pinfunction "PB14_P$116") (pintype "bidirectional"))
    )
    (net (code "104") (name "unconnected-(U$1B-PB15-PadP$115)") (class "Default")
      (node (ref "U$1") (pin "P$115") (pinfunction "PB15_P$115") (pintype "bidirectional"))
    )
    (net (code "105") (name "unconnected-(U$1B-PC0-PadP$78)") (class "Default")
      (node (ref "U$1") (pin "P$78") (pinfunction "PC0_P$78") (pintype "bidirectional"))
    )
    (net (code "106") (name "unconnected-(U$1B-PC1-PadP$77)") (class "Default")
      (node (ref "U$1") (pin "P$77") (pinfunction "PC1_P$77") (pintype "bidirectional"))
    )
    (net (code "107") (name "unconnected-(U$1B-PC2-PadP$80)") (class "Default")
      (node (ref "U$1") (pin "P$80") (pinfunction "PC2_P$80") (pintype "bidirectional"))
    )
    (net (code "108") (name "unconnected-(U$1B-PC3-PadP$79)") (class "Default")
      (node (ref "U$1") (pin "P$79") (pinfunction "PC3_P$79") (pintype "bidirectional"))
    )
    (net (code "109") (name "unconnected-(U$1B-PC4-PadP$90)") (class "Default")
      (node (ref "U$1") (pin "P$90") (pinfunction "PC4_P$90") (pintype "bidirectional"))
    )
    (net (code "110") (name "unconnected-(U$1B-PC5-PadP$89)") (class "Default")
      (node (ref "U$1") (pin "P$89") (pinfunction "PC5_P$89") (pintype "bidirectional"))
    )
    (net (code "111") (name "unconnected-(U$1B-PD8-PadP$118)") (class "Default")
      (node (ref "U$1") (pin "P$118") (pinfunction "PD8_P$118") (pintype "bidirectional"))
    )
    (net (code "112") (name "unconnected-(U$1B-PD9-PadP$117)") (class "Default")
      (node (ref "U$1") (pin "P$117") (pinfunction "PD9_P$117") (pintype "bidirectional"))
    )
    (net (code "113") (name "unconnected-(U$1B-PD10-PadP$120)") (class "Default")
      (node (ref "U$1") (pin "P$120") (pinfunction "PD10_P$120") (pintype "bidirectional"))
    )
    (net (code "114") (name "unconnected-(U$1B-PD11-PadP$119)") (class "Default")
      (node (ref "U$1") (pin "P$119") (pinfunction "PD11_P$119") (pintype "bidirectional"))
    )
    (net (code "115") (name "unconnected-(U$1B-PD12-PadP$122)") (class "Default")
      (node (ref "U$1") (pin "P$122") (pinfunction "PD12_P$122") (pintype "bidirectional"))
    )
    (net (code "116") (name "unconnected-(U$1B-PD13-PadP$121)") (class "Default")
      (node (ref "U$1") (pin "P$121") (pinfunction "PD13_P$121") (pintype "bidirectional"))
    )
    (net (code "117") (name "unconnected-(U$1B-PD14-PadP$124)") (class "Default")
      (node (ref "U$1") (pin "P$124") (pinfunction "PD14_P$124") (pintype "bidirectional"))
    )
    (net (code "118") (name "unconnected-(U$1B-PD15-PadP$123)") (class "Default")
      (node (ref "U$1") (pin "P$123") (pinfunction "PD15_P$123") (pintype "bidirectional"))
    )
    (net (code "119") (name "unconnected-(U$1B-PE7-PadP$101)") (class "Default")
      (node (ref "U$1") (pin "P$101") (pinfunction "PE7_P$101") (pintype "bidirectional"))
    )
    (net (code "120") (name "unconnected-(U$1B-PE8-PadP$104)") (class "Default")
      (node (ref "U$1") (pin "P$104") (pinfunction "PE8_P$104") (pintype "bidirectional"))
    )
    (net (code "121") (name "unconnected-(U$1B-PE9-PadP$103)") (class "Default")
      (node (ref "U$1") (pin "P$103") (pinfunction "PE9_P$103") (pintype "bidirectional"))
    )
    (net (code "122") (name "unconnected-(U$1B-PE10-PadP$106)") (class "Default")
      (node (ref "U$1") (pin "P$106") (pinfunction "PE10_P$106") (pintype "bidirectional"))
    )
    (net (code "123") (name "unconnected-(U$1B-PE11-PadP$105)") (class "Default")
      (node (ref "U$1") (pin "P$105") (pinfunction "PE11_P$105") (pintype "bidirectional"))
    )
    (net (code "124") (name "unconnected-(U$1B-PE12-PadP$108)") (class "Default")
      (node (ref "U$1") (pin "P$108") (pinfunction "PE12_P$108") (pintype "bidirectional"))
    )
    (net (code "125") (name "unconnected-(U$1B-PE13-PadP$107)") (class "Default")
      (node (ref "U$1") (pin "P$107") (pinfunction "PE13_P$107") (pintype "bidirectional"))
    )
    (net (code "126") (name "unconnected-(U$1B-PE14-PadP$110)") (class "Default")
      (node (ref "U$1") (pin "P$110") (pinfunction "PE14_P$110") (pintype "bidirectional"))
    )
    (net (code "127") (name "unconnected-(U$1B-PE15-PadP$109)") (class "Default")
      (node (ref "U$1") (pin "P$109") (pinfunction "PE15_P$109") (pintype "bidirectional"))
    )
    (net (code "128") (name "unconnected-(U$1B-PF6-PadP$67)") (class "Default")
      (node (ref "U$1") (pin "P$67") (pinfunction "PF6_P$67") (pintype "bidirectional"))
    )
    (net (code "129") (name "unconnected-(U$1B-PF7-PadP$70)") (class "Default")
      (node (ref "U$1") (pin "P$70") (pinfunction "PF7_P$70") (pintype "bidirectional"))
    )
    (net (code "130") (name "unconnected-(U$1B-PF8-PadP$69)") (class "Default")
      (node (ref "U$1") (pin "P$69") (pinfunction "PF8_P$69") (pintype "bidirectional"))
    )
    (net (code "131") (name "unconnected-(U$1B-PF9-PadP$72)") (class "Default")
      (node (ref "U$1") (pin "P$72") (pinfunction "PF9_P$72") (pintype "bidirectional"))
    )
    (net (code "132") (name "unconnected-(U$1B-PF10-PadP$71)") (class "Default")
      (node (ref "U$1") (pin "P$71") (pinfunction "PF10_P$71") (pintype "bidirectional"))
    )
    (net (code "133") (name "unconnected-(U$1B-PF11-PadP$96)") (class "Default")
      (node (ref "U$1") (pin "P$96") (pinfunction "PF11_P$96") (pintype "bidirectional"))
    )
    (net (code "134") (name "unconnected-(U$1B-PF12-PadP$95)") (class "Default")
      (node (ref "U$1") (pin "P$95") (pinfunction "PF12_P$95") (pintype "bidirectional"))
    )
    (net (code "135") (name "unconnected-(U$1B-PF13-PadP$98)") (class "Default")
      (node (ref "U$1") (pin "P$98") (pinfunction "PF13_P$98") (pintype "bidirectional"))
    )
    (net (code "136") (name "unconnected-(U$1B-PF14-PadP$97)") (class "Default")
      (node (ref "U$1") (pin "P$97") (pinfunction "PF14_P$97") (pintype "bidirectional"))
    )
    (net (code "137") (name "unconnected-(U$1B-PF15-PadP$100)") (class "Default")
      (node (ref "U$1") (pin "P$100") (pinfunction "PF15_P$100") (pintype "bidirectional"))
    )
    (net (code "138") (name "unconnected-(U$1B-PG0-PadP$99)") (class "Default")
      (node (ref "U$1") (pin "P$99") (pinfunction "PG0_P$99") (pintype "bidirectional"))
    )
    (net (code "139") (name "unconnected-(U$1B-PG1-PadP$102)") (class "Default")
      (node (ref "U$1") (pin "P$102") (pinfunction "PG1_P$102") (pintype "bidirectional"))
    )
    (net (code "140") (name "unconnected-(U$1B-PG2-PadP$126)") (class "Default")
      (node (ref "U$1") (pin "P$126") (pinfunction "PG2_P$126") (pintype "bidirectional"))
    )
    (net (code "141") (name "unconnected-(U$1B-PG3-PadP$125)") (class "Default")
      (node (ref "U$1") (pin "P$125") (pinfunction "PG3_P$125") (pintype "bidirectional"))
    )
    (net (code "142") (name "unconnected-(U$1B-PH0-PadP$74)") (class "Default")
      (node (ref "U$1") (pin "P$74") (pinfunction "PH0_P$74") (pintype "bidirectional"))
    )
    (net (code "143") (name "unconnected-(U$1B-PH1-PadP$73)") (class "Default")
      (node (ref "U$1") (pin "P$73") (pinfunction "PH1_P$73") (pintype "bidirectional"))
    )
    (net (code "144") (name "unconnected-(U$17-P$7-Pad7)") (class "Default")
      (node (ref "U$17") (pin "7") (pinfunction "P$7_7") (pintype "input"))
    )
    (net (code "145") (name "unconnected-(U1-NC-Pad7)") (class "Default")
      (node (ref "U1") (pin "7") (pinfunction "NC_7") (pintype "bidirectional"))
    )
    (net (code "146") (name "unconnected-(U1-NC-Pad8)") (class "Default")
      (node (ref "U1") (pin "8") (pinfunction "NC_8") (pintype "bidirectional"))
    )
    (net (code "147") (name "unconnected-(U1-NC-VCC-Pad10)") (class "Default")
      (node (ref "U1") (pin "10") (pinfunction "NC-VCC_10") (pintype "bidirectional"))
    )
    (net (code "148") (name "unconnected-(U1-P0_6-Pad16)") (class "Default")
      (node (ref "U1") (pin "16") (pinfunction "P0_6_16") (pintype "bidirectional"))
    )
    (net (code "149") (name "unconnected-(U1-P0_7-Pad15)") (class "Default")
      (node (ref "U1") (pin "15") (pinfunction "P0_7_15") (pintype "bidirectional"))
    )
    (net (code "150") (name "unconnected-(U1-P1_0-Pad14)") (class "Default")
      (node (ref "U1") (pin "14") (pinfunction "P1_0_14") (pintype "bidirectional"))
    )
    (net (code "151") (name "unconnected-(U1-P1_1-Pad13)") (class "Default")
      (node (ref "U1") (pin "13") (pinfunction "P1_1_13") (pintype "bidirectional"))
    )
    (net (code "152") (name "unconnected-(U1-P1_4-CTS-Pad3)") (class "Default")
      (node (ref "U1") (pin "3") (pinfunction "P1_4-CTS_3") (pintype "bidirectional"))
    )
    (net (code "153") (name "unconnected-(U1-P1_5-RTS-Pad1)") (class "Default")
      (node (ref "U1") (pin "1") (pinfunction "P1_5-RTS_1") (pintype "bidirectional"))
    )
    (net (code "154") (name "unconnected-(U1-P2_1-NC-Pad5)") (class "Default")
      (node (ref "U1") (pin "5") (pinfunction "P2_1-NC_5") (pintype "bidirectional"))
    )
    (net (code "155") (name "unconnected-(U1-P2_2-NC-Pad6)") (class "Default")
      (node (ref "U1") (pin "6") (pinfunction "P2_2-NC_6") (pintype "bidirectional"))
    )
  )
)
